# sb-sonata-psu.net
KiCad netlist of a schematic drawn in Altium Designer
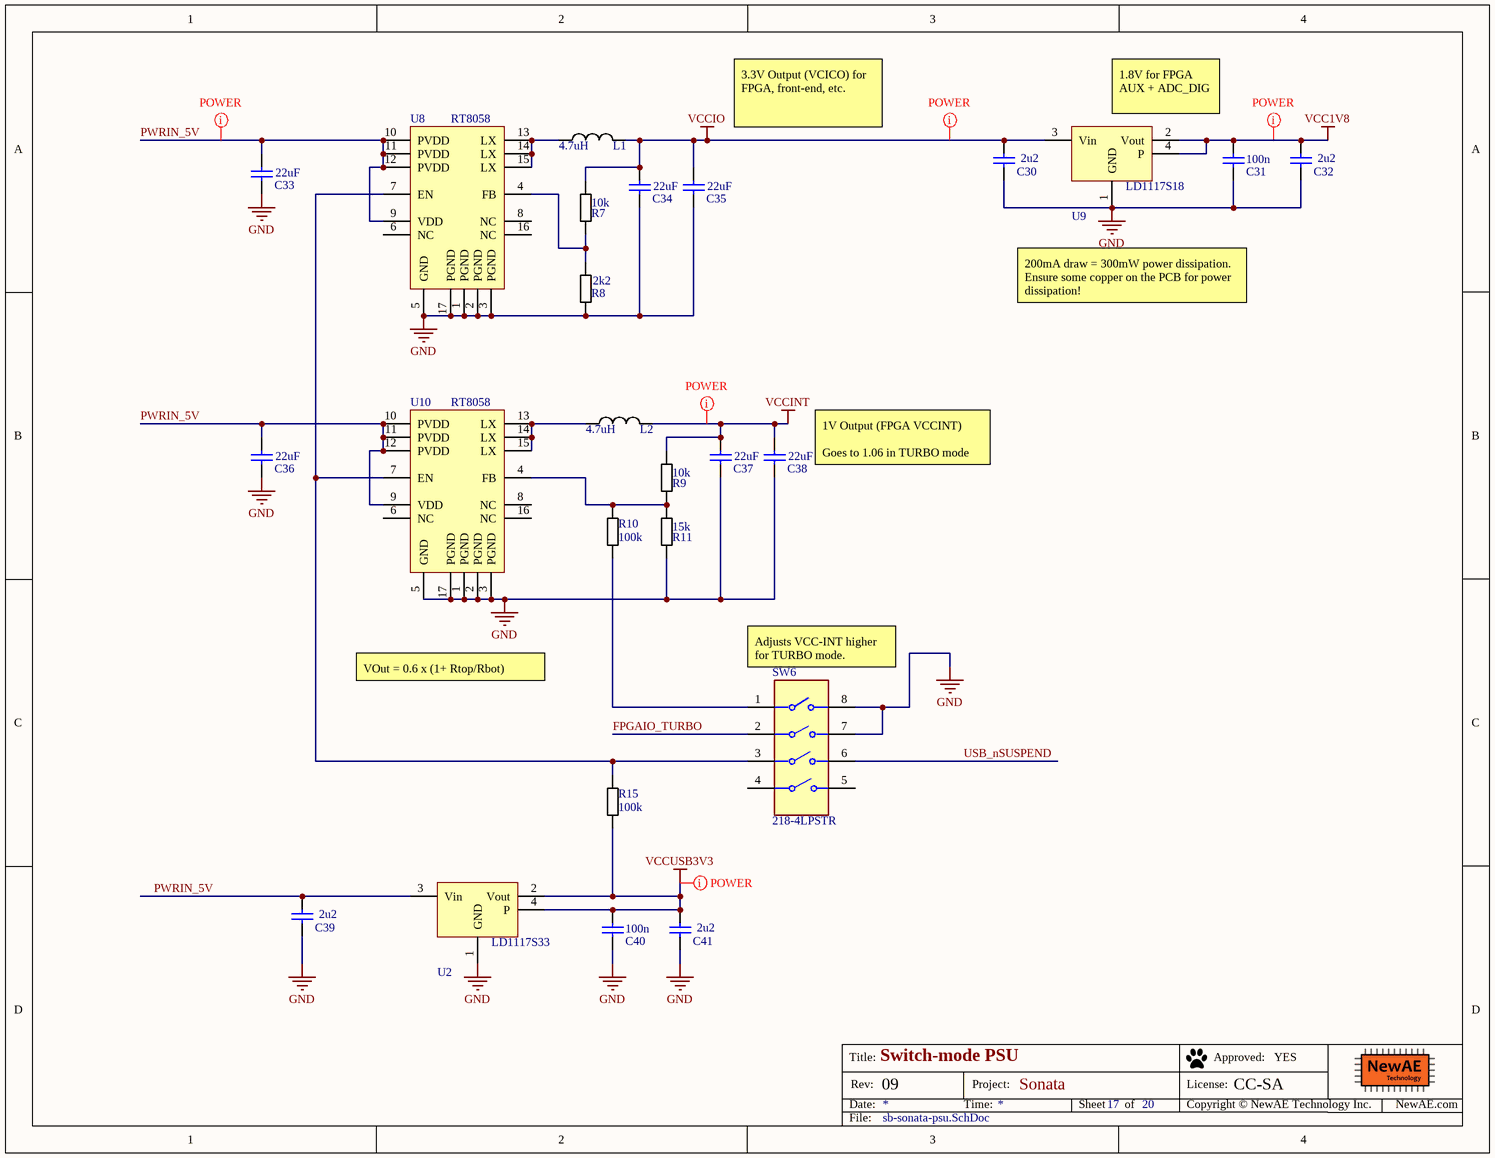
[diagram p0: sb-sonata-psu.SchDoc]

(export (version "E")
  (design (tool "Eeschema 10.0.6"))
  (components
    (comp (ref "C30")
      (value "2u2")
      (footprint "CAPC0603_M")
      (description "2u2, 0603")
      (fields (field (name "PART NUMBER") "CCHIP-2u2-0603"))
      (libsource (lib "NewAE_AltiumLib") (part "CAP"))
    )
    (comp (ref "C31")
      (value "100n")
      (footprint "CAPC0402_M")
      (description "100n, 0402")
      (fields (field (name "PART NUMBER") "CCHIP-100n-0402"))
      (libsource (lib "NewAE_AltiumLib") (part "CAP"))
    )
    (comp (ref "C32")
      (value "2u2")
      (footprint "CAPC0603_M")
      (description "2u2, 0603")
      (fields (field (name "PART NUMBER") "CCHIP-2u2-0603"))
      (libsource (lib "NewAE_AltiumLib") (part "CAP"))
    )
    (comp (ref "C33")
      (value "22uF")
      (footprint "CAPC0805_M")
      (description "22u, 16V, 0805, Ceramic")
      (fields (field (name "PART NUMBER") "CCHIP-22u-0805-16V") (field (name "TOLERANCE") "20%"))
      (libsource (lib "NewAE_AltiumLib") (part "CAP"))
    )
    (comp (ref "C34")
      (value "22uF")
      (footprint "CAPC0805_M")
      (description "22u, 16V, 0805, Ceramic")
      (fields (field (name "PART NUMBER") "CCHIP-22u-0805-16V") (field (name "TOLERANCE") "20%"))
      (libsource (lib "NewAE_AltiumLib") (part "CAP"))
    )
    (comp (ref "C35")
      (value "22uF")
      (footprint "CAPC0805_M")
      (description "22u, 16V, 0805, Ceramic")
      (fields (field (name "PART NUMBER") "CCHIP-22u-0805-16V") (field (name "TOLERANCE") "20%"))
      (libsource (lib "NewAE_AltiumLib") (part "CAP"))
    )
    (comp (ref "C36")
      (value "22uF")
      (footprint "CAPC0805_M")
      (description "22u, 16V, 0805, Ceramic")
      (fields (field (name "PART NUMBER") "CCHIP-22u-0805-16V") (field (name "TOLERANCE") "20%"))
      (libsource (lib "NewAE_AltiumLib") (part "CAP"))
    )
    (comp (ref "C37")
      (value "22uF")
      (footprint "CAPC0805_M")
      (description "22u, 16V, 0805, Ceramic")
      (fields (field (name "PART NUMBER") "CCHIP-22u-0805-16V") (field (name "TOLERANCE") "20%"))
      (libsource (lib "NewAE_AltiumLib") (part "CAP"))
    )
    (comp (ref "C38")
      (value "22uF")
      (footprint "CAPC0805_M")
      (description "22u, 16V, 0805, Ceramic")
      (fields (field (name "PART NUMBER") "CCHIP-22u-0805-16V") (field (name "TOLERANCE") "20%"))
      (libsource (lib "NewAE_AltiumLib") (part "CAP"))
    )
    (comp (ref "C39")
      (value "2u2")
      (footprint "CAPC0603_M")
      (description "2u2, 0603")
      (fields (field (name "PART NUMBER") "CCHIP-2u2-0603"))
      (libsource (lib "NewAE_AltiumLib") (part "CAP"))
    )
    (comp (ref "C40")
      (value "100n")
      (footprint "CAPC0402_M")
      (description "100n, 0402")
      (fields (field (name "PART NUMBER") "CCHIP-100n-0402"))
      (libsource (lib "NewAE_AltiumLib") (part "CAP"))
    )
    (comp (ref "C41")
      (value "2u2")
      (footprint "CAPC0603_M")
      (description "2u2, 0603")
      (fields (field (name "PART NUMBER") "CCHIP-2u2-0603"))
      (libsource (lib "NewAE_AltiumLib") (part "CAP"))
    )
    (comp (ref "L1")
      (value "4.7uH")
      (footprint "NR6028")
      (description "fixed ind, ferrite, shielded")
      (fields (field (name "PART NUMBER") "NR6028T4R7M"))
      (libsource (lib "NewAE_AltiumLib") (part "IND"))
    )
    (comp (ref "L2")
      (value "4.7uH")
      (footprint "NR6028")
      (description "fixed ind, ferrite, shielded")
      (fields (field (name "PART NUMBER") "NR6028T4R7M"))
      (libsource (lib "NewAE_AltiumLib") (part "IND"))
    )
    (comp (ref "R7")
      (value "10k")
      (footprint "RESC1005X40N")
      (description "10k res, 0402, 1%, 1/16W")
      (fields (field (name "PART NUMBER") "RCHIP-10K-0402") (field (name "TOLERANCE") "1%"))
      (libsource (lib "") (part "RES-EU_1"))
    )
    (comp (ref "R8")
      (value "2k2")
      (footprint "RESC1005X40N")
      (description "2k2 res, 0402, 1%, 1/16W")
      (fields (field (name "PART NUMBER") "RCHIP-2K2-0402") (field (name "TOLERANCE") "1%"))
      (libsource (lib "") (part "RES-EU_1"))
    )
    (comp (ref "R9")
      (value "10k")
      (footprint "RESC1005X40N")
      (description "10k res, 0402, 1%, 1/16W")
      (fields (field (name "PART NUMBER") "RCHIP-10K-0402") (field (name "TOLERANCE") "1%"))
      (libsource (lib "") (part "RES-EU_1"))
    )
    (comp (ref "R10")
      (value "100k")
      (footprint "RESC1005X40N")
      (description "100k res, 0402, 1%, 1/16W")
      (fields (field (name "PART NUMBER") "RCHIP-100K-0402") (field (name "TOLERANCE") "1%"))
      (libsource (lib "") (part "RES-EU_1"))
    )
    (comp (ref "R11")
      (value "15k")
      (footprint "RESC1005X40N")
      (description "15k res, 0402, 1%, 1/16W")
      (fields (field (name "PART NUMBER") "RCHIP-15K-0402") (field (name "TOLERANCE") "1%"))
      (libsource (lib "") (part "RES-EU_1"))
    )
    (comp (ref "R15")
      (value "100k")
      (footprint "RESC1608X55N")
      (description "100k res, 0603, 1%, 1/10W")
      (fields (field (name "PART NUMBER") "RCHIP-100K-0603") (field (name "TOLERANCE") "1%"))
      (libsource (lib "NewAE_AltiumLib") (part "RES-EU"))
    )
    (comp (ref "SW6")
      (value "218-4LPSTR")
      (footprint "FP-218-4LPSTR-MFG")
      (description "SWITCH SLIDE DIP SPST 25MA 24V")
      (libsource (lib "Altium Content Vault") (part "a78650ae27aee94b64e9c93150c7d5d"))
    )
    (comp (ref "U2")
      (value "LD1117S33")
      (footprint "SOT-223")
      (description "IC REG LIN POS 3.3V 800MA SOT223")
      (libsource (lib "NewAE_AltiumLib") (part "LD1117S33"))
    )
    (comp (ref "U8")
      (value "RT8058")
      (footprint "QFN16_50P300X300X100_HS-17M")
      (description "Switching supply controller, 2A")
      (libsource (lib "NewAE_AltiumLib") (part "RT8058"))
    )
    (comp (ref "U9")
      (value "LD1117S18")
      (footprint "SOT-223")
      (description "IC REG LIN POS 1.8V 800MA SOT223")
      (libsource (lib "NewAE_AltiumLib") (part "LD1117S33"))
    )
    (comp (ref "U10")
      (value "RT8058")
      (footprint "QFN16_50P300X300X100_HS-17M")
      (description "Switching supply controller, 2A")
      (libsource (lib "NewAE_AltiumLib") (part "RT8058"))
    )
  )
  (nets
    (net (code "1") (name "/FPGAIO_TURBO") (class "Default")
      (node (ref "SW6") (pin "2") (pinfunction "2_2") (pintype "passive"))
    )
    (net (code "2") (name "/PWRIN_5V") (class "Default")
      (node (ref "C33") (pin "1") (pinfunction "1_1") (pintype "passive"))
      (node (ref "C36") (pin "1") (pinfunction "1_1") (pintype "passive"))
      (node (ref "C39") (pin "1") (pinfunction "1_1") (pintype "passive"))
      (node (ref "U10") (pin "10") (pinfunction "PVDD_10") (pintype "passive"))
      (node (ref "U10") (pin "11") (pinfunction "PVDD_11") (pintype "passive"))
      (node (ref "U10") (pin "12") (pinfunction "PVDD_12") (pintype "passive"))
      (node (ref "U10") (pin "9") (pinfunction "VDD_9") (pintype "passive"))
      (node (ref "U2") (pin "3") (pinfunction "Vin_3") (pintype "passive"))
      (node (ref "U8") (pin "10") (pinfunction "PVDD_10") (pintype "passive"))
      (node (ref "U8") (pin "11") (pinfunction "PVDD_11") (pintype "passive"))
      (node (ref "U8") (pin "12") (pinfunction "PVDD_12") (pintype "passive"))
      (node (ref "U8") (pin "9") (pinfunction "VDD_9") (pintype "passive"))
    )
    (net (code "3") (name "/USB_nSUSPEND") (class "Default")
      (node (ref "SW6") (pin "6") (pinfunction "6_6") (pintype "passive"))
    )
    (net (code "4") (name "GND") (class "Default")
      (node (ref "C30") (pin "2") (pinfunction "2_2") (pintype "passive"))
      (node (ref "C31") (pin "2") (pinfunction "2_2") (pintype "passive"))
      (node (ref "C32") (pin "2") (pinfunction "2_2") (pintype "passive"))
      (node (ref "C33") (pin "2") (pinfunction "2_2") (pintype "passive"))
      (node (ref "C34") (pin "2") (pinfunction "2_2") (pintype "passive"))
      (node (ref "C35") (pin "2") (pinfunction "2_2") (pintype "passive"))
      (node (ref "C36") (pin "2") (pinfunction "2_2") (pintype "passive"))
      (node (ref "C37") (pin "2") (pinfunction "2_2") (pintype "passive"))
      (node (ref "C38") (pin "2") (pinfunction "2_2") (pintype "passive"))
      (node (ref "C39") (pin "2") (pinfunction "2_2") (pintype "passive"))
      (node (ref "C40") (pin "2") (pinfunction "2_2") (pintype "passive"))
      (node (ref "C41") (pin "2") (pinfunction "2_2") (pintype "passive"))
      (node (ref "R11") (pin "2") (pinfunction "2_2") (pintype "passive"))
      (node (ref "R8") (pin "2") (pinfunction "2_2") (pintype "passive"))
      (node (ref "SW6") (pin "7") (pinfunction "7_7") (pintype "passive"))
      (node (ref "SW6") (pin "8") (pinfunction "8_8") (pintype "passive"))
      (node (ref "U10") (pin "1") (pinfunction "PGND_1") (pintype "passive"))
      (node (ref "U10") (pin "17") (pinfunction "PGND_17") (pintype "passive"))
      (node (ref "U10") (pin "2") (pinfunction "PGND_2") (pintype "passive"))
      (node (ref "U10") (pin "3") (pinfunction "PGND_3") (pintype "passive"))
      (node (ref "U10") (pin "5") (pinfunction "GND_5") (pintype "passive"))
      (node (ref "U2") (pin "1") (pinfunction "GND_1") (pintype "passive"))
      (node (ref "U8") (pin "1") (pinfunction "PGND_1") (pintype "passive"))
      (node (ref "U8") (pin "17") (pinfunction "PGND_17") (pintype "passive"))
      (node (ref "U8") (pin "2") (pinfunction "PGND_2") (pintype "passive"))
      (node (ref "U8") (pin "3") (pinfunction "PGND_3") (pintype "passive"))
      (node (ref "U8") (pin "5") (pinfunction "GND_5") (pintype "passive"))
      (node (ref "U9") (pin "1") (pinfunction "GND_1") (pintype "passive"))
    )
    (net (code "5") (name "Net-(L1-Pad1)") (class "Default")
      (node (ref "L1") (pin "1") (pinfunction "1_1") (pintype "passive"))
      (node (ref "U8") (pin "13") (pinfunction "LX_13") (pintype "passive"))
      (node (ref "U8") (pin "14") (pinfunction "LX_14") (pintype "passive"))
      (node (ref "U8") (pin "15") (pinfunction "LX_15") (pintype "passive"))
    )
    (net (code "6") (name "Net-(L2-Pad1)") (class "Default")
      (node (ref "L2") (pin "1") (pinfunction "1_1") (pintype "passive"))
      (node (ref "U10") (pin "13") (pinfunction "LX_13") (pintype "passive"))
      (node (ref "U10") (pin "14") (pinfunction "LX_14") (pintype "passive"))
      (node (ref "U10") (pin "15") (pinfunction "LX_15") (pintype "passive"))
    )
    (net (code "7") (name "Net-(R10-Pad2)") (class "Default")
      (node (ref "R10") (pin "2") (pinfunction "2_2") (pintype "passive"))
      (node (ref "SW6") (pin "1") (pinfunction "1_1") (pintype "passive"))
    )
    (net (code "8") (name "Net-(U8-FB)") (class "Default")
      (node (ref "R7") (pin "2") (pinfunction "2_2") (pintype "passive"))
      (node (ref "R8") (pin "1") (pinfunction "1_1") (pintype "passive"))
      (node (ref "U8") (pin "4") (pinfunction "FB_4") (pintype "passive"))
    )
    (net (code "9") (name "Net-(U10-EN)") (class "Default")
      (node (ref "R15") (pin "2") (pinfunction "2_2") (pintype "passive"))
      (node (ref "SW6") (pin "3") (pinfunction "3_3") (pintype "passive"))
      (node (ref "U10") (pin "7") (pinfunction "EN_7") (pintype "passive"))
      (node (ref "U8") (pin "7") (pinfunction "EN_7") (pintype "passive"))
    )
    (net (code "10") (name "Net-(U10-FB)") (class "Default")
      (node (ref "R10") (pin "1") (pinfunction "1_1") (pintype "passive"))
      (node (ref "R11") (pin "1") (pinfunction "1_1") (pintype "passive"))
      (node (ref "R9") (pin "2") (pinfunction "2_2") (pintype "passive"))
      (node (ref "U10") (pin "4") (pinfunction "FB_4") (pintype "passive"))
    )
    (net (code "11") (name "VCC1V8") (class "Default")
      (node (ref "C31") (pin "1") (pinfunction "1_1") (pintype "passive"))
      (node (ref "C32") (pin "1") (pinfunction "1_1") (pintype "passive"))
      (node (ref "U9") (pin "2") (pinfunction "Vout_2") (pintype "passive"))
      (node (ref "U9") (pin "4") (pinfunction "P_4") (pintype "passive"))
    )
    (net (code "12") (name "VCCINT") (class "Default")
      (node (ref "C37") (pin "1") (pinfunction "1_1") (pintype "passive"))
      (node (ref "C38") (pin "1") (pinfunction "1_1") (pintype "passive"))
      (node (ref "L2") (pin "2") (pinfunction "2_2") (pintype "passive"))
      (node (ref "R9") (pin "1") (pinfunction "1_1") (pintype "passive"))
    )
    (net (code "13") (name "VCCIO") (class "Default")
      (node (ref "C30") (pin "1") (pinfunction "1_1") (pintype "passive"))
      (node (ref "C34") (pin "1") (pinfunction "1_1") (pintype "passive"))
      (node (ref "C35") (pin "1") (pinfunction "1_1") (pintype "passive"))
      (node (ref "L1") (pin "2") (pinfunction "2_2") (pintype "passive"))
      (node (ref "R7") (pin "1") (pinfunction "1_1") (pintype "passive"))
      (node (ref "U9") (pin "3") (pinfunction "Vin_3") (pintype "passive"))
    )
    (net (code "14") (name "VCCUSB3V3") (class "Default")
      (node (ref "C40") (pin "1") (pinfunction "1_1") (pintype "passive"))
      (node (ref "C41") (pin "1") (pinfunction "1_1") (pintype "passive"))
      (node (ref "R15") (pin "1") (pinfunction "1_1") (pintype "passive"))
      (node (ref "U2") (pin "2") (pinfunction "Vout_2") (pintype "passive"))
      (node (ref "U2") (pin "4") (pinfunction "P_4") (pintype "passive"))
    )
    (net (code "15") (name "unconnected-(SW6-Pad4)") (class "Default")
      (node (ref "SW6") (pin "4") (pinfunction "4_4") (pintype "passive"))
    )
    (net (code "16") (name "unconnected-(SW6-Pad5)") (class "Default")
      (node (ref "SW6") (pin "5") (pinfunction "5_5") (pintype "passive"))
    )
    (net (code "17") (name "unconnected-(U8-NC-Pad6)") (class "Default")
      (node (ref "U8") (pin "6") (pinfunction "NC_6") (pintype "passive"))
    )
    (net (code "18") (name "unconnected-(U8-NC-Pad8)") (class "Default")
      (node (ref "U8") (pin "8") (pinfunction "NC_8") (pintype "passive"))
    )
    (net (code "19") (name "unconnected-(U8-NC-Pad16)") (class "Default")
      (node (ref "U8") (pin "16") (pinfunction "NC_16") (pintype "passive"))
    )
    (net (code "20") (name "unconnected-(U10-NC-Pad6)") (class "Default")
      (node (ref "U10") (pin "6") (pinfunction "NC_6") (pintype "passive"))
    )
    (net (code "21") (name "unconnected-(U10-NC-Pad8)") (class "Default")
      (node (ref "U10") (pin "8") (pinfunction "NC_8") (pintype "passive"))
    )
    (net (code "22") (name "unconnected-(U10-NC-Pad16)") (class "Default")
      (node (ref "U10") (pin "16") (pinfunction "NC_16") (pintype "passive"))
    )
  )
)
